# potmeters.net
KiCad netlist of a schematic drawn in Altium Designer
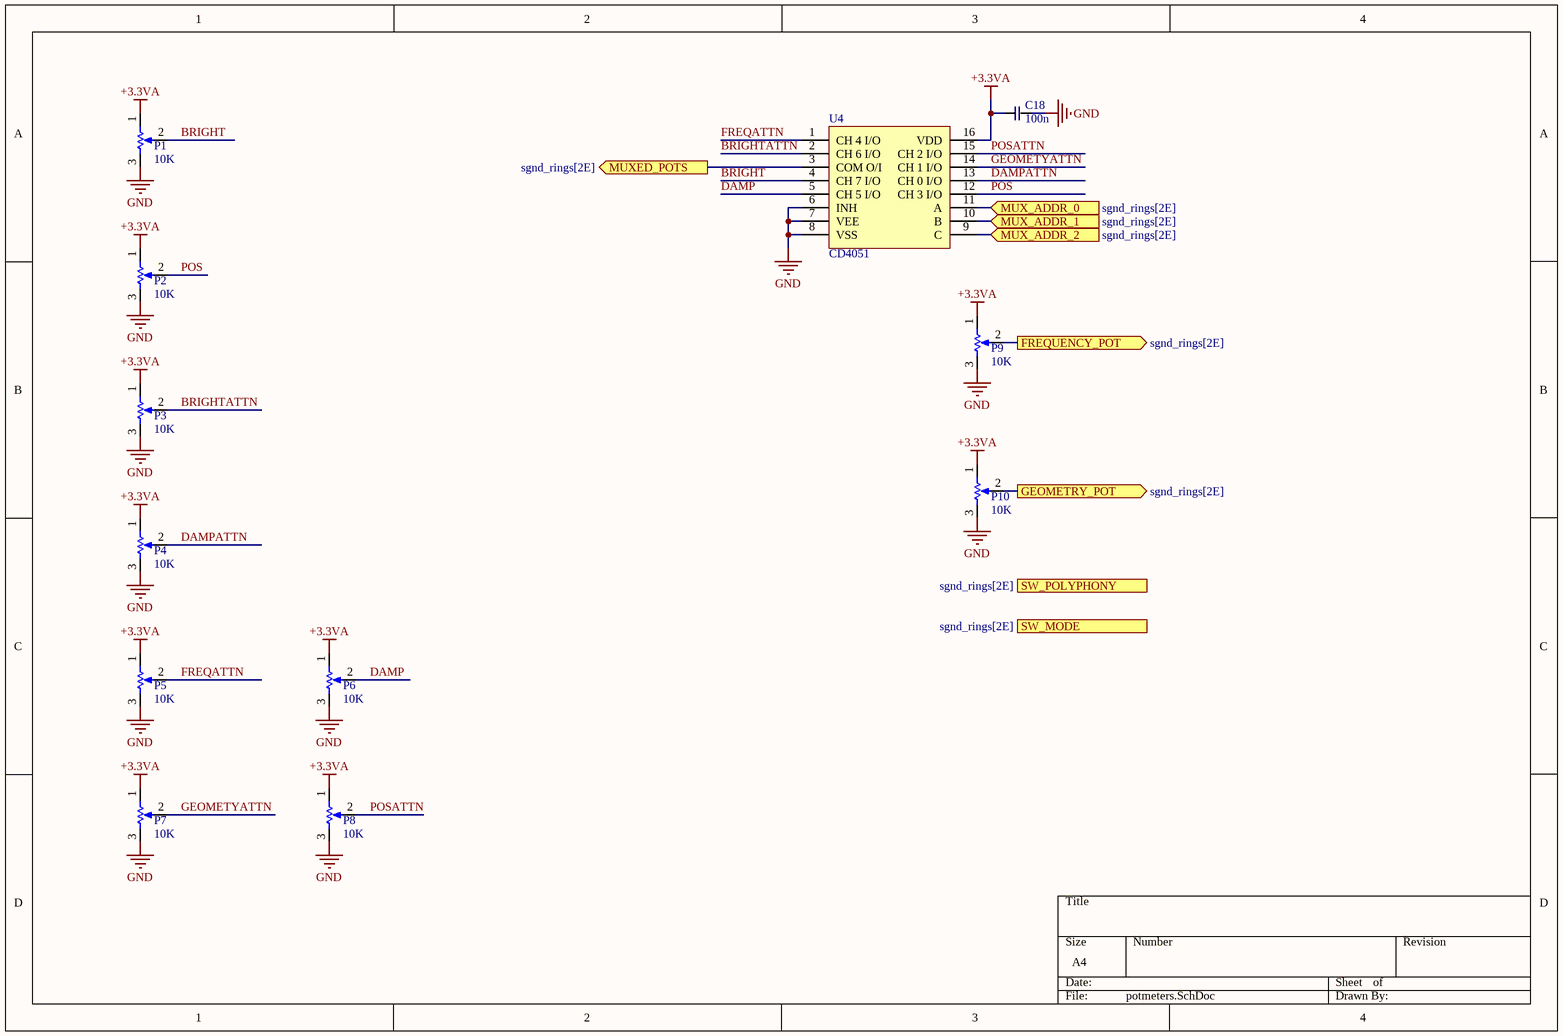
[diagram p0: potmeters.SchDoc]

(export (version "E")
  (design (tool "Eeschema 10.0.6"))
  (components
    (comp (ref "C18")
      (value "100n")
      (footprint "C0603")
      (description "Capacitor (Semiconductor SIM Model)")
      (fields (field (name "Comment") "Capacitor") (field (name "PUBLISHER") "Altium Limited"))
      (libsource (lib "ryzerd") (part "Capacitor"))
    )
    (comp (ref "P1")
      (value "10K")
      (footprint "Potentiometer_vertical")
      (description "Potentiometer")
      (fields (field (name "Comment") "BRIGHT") (field (name "PUBLISHER") "Altium Limited"))
      (libsource (lib "ryzerd") (part "RPot"))
    )
    (comp (ref "P2")
      (value "10K")
      (footprint "Potentiometer_vertical")
      (description "Potentiometer")
      (fields (field (name "Comment") "BRIGHT") (field (name "PUBLISHER") "Altium Limited"))
      (libsource (lib "ryzerd") (part "RPot"))
    )
    (comp (ref "P3")
      (value "10K")
      (footprint "Potentiometer_vertical")
      (description "Potentiometer")
      (fields (field (name "Comment") "BRIGHT") (field (name "PUBLISHER") "Altium Limited"))
      (libsource (lib "ryzerd") (part "RPot"))
    )
    (comp (ref "P4")
      (value "10K")
      (footprint "Potentiometer_vertical")
      (description "Potentiometer")
      (fields (field (name "Comment") "BRIGHT") (field (name "PUBLISHER") "Altium Limited"))
      (libsource (lib "ryzerd") (part "RPot"))
    )
    (comp (ref "P5")
      (value "10K")
      (footprint "Potentiometer_vertical")
      (description "Potentiometer")
      (fields (field (name "Comment") "BRIGHT") (field (name "PUBLISHER") "Altium Limited"))
      (libsource (lib "ryzerd") (part "RPot"))
    )
    (comp (ref "P6")
      (value "10K")
      (footprint "Potentiometer_vertical")
      (description "Potentiometer")
      (fields (field (name "Comment") "BRIGHT") (field (name "PUBLISHER") "Altium Limited"))
      (libsource (lib "ryzerd") (part "RPot"))
    )
    (comp (ref "P7")
      (value "10K")
      (footprint "Potentiometer_vertical")
      (description "Potentiometer")
      (fields (field (name "Comment") "BRIGHT") (field (name "PUBLISHER") "Altium Limited"))
      (libsource (lib "ryzerd") (part "RPot"))
    )
    (comp (ref "P8")
      (value "10K")
      (footprint "Potentiometer_vertical")
      (description "Potentiometer")
      (fields (field (name "Comment") "BRIGHT") (field (name "PUBLISHER") "Altium Limited"))
      (libsource (lib "ryzerd") (part "RPot"))
    )
    (comp (ref "P9")
      (value "10K")
      (footprint "Potentiometer_vertical")
      (description "Potentiometer")
      (fields (field (name "Comment") "BRIGHT") (field (name "PUBLISHER") "Altium Limited"))
      (libsource (lib "ryzerd") (part "RPot"))
    )
    (comp (ref "P10")
      (value "10K")
      (footprint "Potentiometer_vertical")
      (description "Potentiometer")
      (fields (field (name "Comment") "BRIGHT") (field (name "PUBLISHER") "Altium Limited"))
      (libsource (lib "ryzerd") (part "RPot"))
    )
    (comp (ref "U4")
      (value "CD4051")
      (footprint "SOP16")
      (description "CD4051 CMOS Single 8-Channel Analog Multiplexer/Demultiplexer  With Logic-Level Conversion")
      (libsource (lib "ryzerd") (part "CD4051"))
    )
  )
  (nets
    (net (code "1") (name "+3.3VA") (class "Default")
      (node (ref "C18") (pin "1") (pinfunction "1_1") (pintype "passive"))
      (node (ref "P1") (pin "1") (pinfunction "BOT_1") (pintype "passive"))
      (node (ref "P10") (pin "1") (pinfunction "BOT_1") (pintype "passive"))
      (node (ref "P2") (pin "1") (pinfunction "BOT_1") (pintype "passive"))
      (node (ref "P3") (pin "1") (pinfunction "BOT_1") (pintype "passive"))
      (node (ref "P4") (pin "1") (pinfunction "BOT_1") (pintype "passive"))
      (node (ref "P5") (pin "1") (pinfunction "BOT_1") (pintype "passive"))
      (node (ref "P6") (pin "1") (pinfunction "BOT_1") (pintype "passive"))
      (node (ref "P7") (pin "1") (pinfunction "BOT_1") (pintype "passive"))
      (node (ref "P8") (pin "1") (pinfunction "BOT_1") (pintype "passive"))
      (node (ref "P9") (pin "1") (pinfunction "BOT_1") (pintype "passive"))
      (node (ref "U4") (pin "16") (pinfunction "VDD_16") (pintype "passive"))
    )
    (net (code "2") (name "/BRIGHT") (class "Default")
      (node (ref "P1") (pin "2") (pinfunction "TAP_2") (pintype "passive"))
      (node (ref "U4") (pin "4") (pinfunction "CH_7_I/O_4") (pintype "passive"))
    )
    (net (code "3") (name "/BRIGHTATTN") (class "Default")
      (node (ref "P3") (pin "2") (pinfunction "TAP_2") (pintype "passive"))
      (node (ref "U4") (pin "2") (pinfunction "CH_6_I/O_2") (pintype "passive"))
    )
    (net (code "4") (name "/DAMP") (class "Default")
      (node (ref "P6") (pin "2") (pinfunction "TAP_2") (pintype "passive"))
      (node (ref "U4") (pin "5") (pinfunction "CH_5_I/O_5") (pintype "passive"))
    )
    (net (code "5") (name "/DAMPATTN") (class "Default")
      (node (ref "P4") (pin "2") (pinfunction "TAP_2") (pintype "passive"))
      (node (ref "U4") (pin "13") (pinfunction "CH_0_I/O_13") (pintype "passive"))
    )
    (net (code "6") (name "/FREQATTN") (class "Default")
      (node (ref "P5") (pin "2") (pinfunction "TAP_2") (pintype "passive"))
      (node (ref "U4") (pin "1") (pinfunction "CH_4_I/O_1") (pintype "passive"))
    )
    (net (code "7") (name "/FREQUENCY_POT") (class "Default")
      (node (ref "P9") (pin "2") (pinfunction "TAP_2") (pintype "passive"))
    )
    (net (code "8") (name "/GEOMETRY_POT") (class "Default")
      (node (ref "P10") (pin "2") (pinfunction "TAP_2") (pintype "passive"))
    )
    (net (code "9") (name "/GEOMETYATTN") (class "Default")
      (node (ref "P7") (pin "2") (pinfunction "TAP_2") (pintype "passive"))
      (node (ref "U4") (pin "14") (pinfunction "CH_1_I/O_14") (pintype "passive"))
    )
    (net (code "10") (name "/MUXED_POTS") (class "Default")
      (node (ref "U4") (pin "3") (pinfunction "COM_O/I_3") (pintype "passive"))
    )
    (net (code "11") (name "/MUX_ADDR_0") (class "Default")
      (node (ref "U4") (pin "11") (pinfunction "A_11") (pintype "passive"))
    )
    (net (code "12") (name "/MUX_ADDR_1") (class "Default")
      (node (ref "U4") (pin "10") (pinfunction "B_10") (pintype "passive"))
    )
    (net (code "13") (name "/MUX_ADDR_2") (class "Default")
      (node (ref "U4") (pin "9") (pinfunction "C_9") (pintype "passive"))
    )
    (net (code "14") (name "/POS") (class "Default")
      (node (ref "P2") (pin "2") (pinfunction "TAP_2") (pintype "passive"))
      (node (ref "U4") (pin "12") (pinfunction "CH_3_I/O_12") (pintype "passive"))
    )
    (net (code "15") (name "/POSATTN") (class "Default")
      (node (ref "P8") (pin "2") (pinfunction "TAP_2") (pintype "passive"))
      (node (ref "U4") (pin "15") (pinfunction "CH_2_I/O_15") (pintype "passive"))
    )
    (net (code "18") (name "GND") (class "Default")
      (node (ref "C18") (pin "2") (pinfunction "2_2") (pintype "passive"))
      (node (ref "P1") (pin "3") (pinfunction "TOP_3") (pintype "passive"))
      (node (ref "P10") (pin "3") (pinfunction "TOP_3") (pintype "passive"))
      (node (ref "P2") (pin "3") (pinfunction "TOP_3") (pintype "passive"))
      (node (ref "P3") (pin "3") (pinfunction "TOP_3") (pintype "passive"))
      (node (ref "P4") (pin "3") (pinfunction "TOP_3") (pintype "passive"))
      (node (ref "P5") (pin "3") (pinfunction "TOP_3") (pintype "passive"))
      (node (ref "P6") (pin "3") (pinfunction "TOP_3") (pintype "passive"))
      (node (ref "P7") (pin "3") (pinfunction "TOP_3") (pintype "passive"))
      (node (ref "P8") (pin "3") (pinfunction "TOP_3") (pintype "passive"))
      (node (ref "P9") (pin "3") (pinfunction "TOP_3") (pintype "passive"))
      (node (ref "U4") (pin "6") (pinfunction "INH_6") (pintype "passive"))
      (node (ref "U4") (pin "7") (pinfunction "VEE_7") (pintype "passive"))
      (node (ref "U4") (pin "8") (pinfunction "VSS_8") (pintype "passive"))
    )
  )
)
